# hv3layerMSP.net
KiCad netlist of a schematic drawn in EAGLE
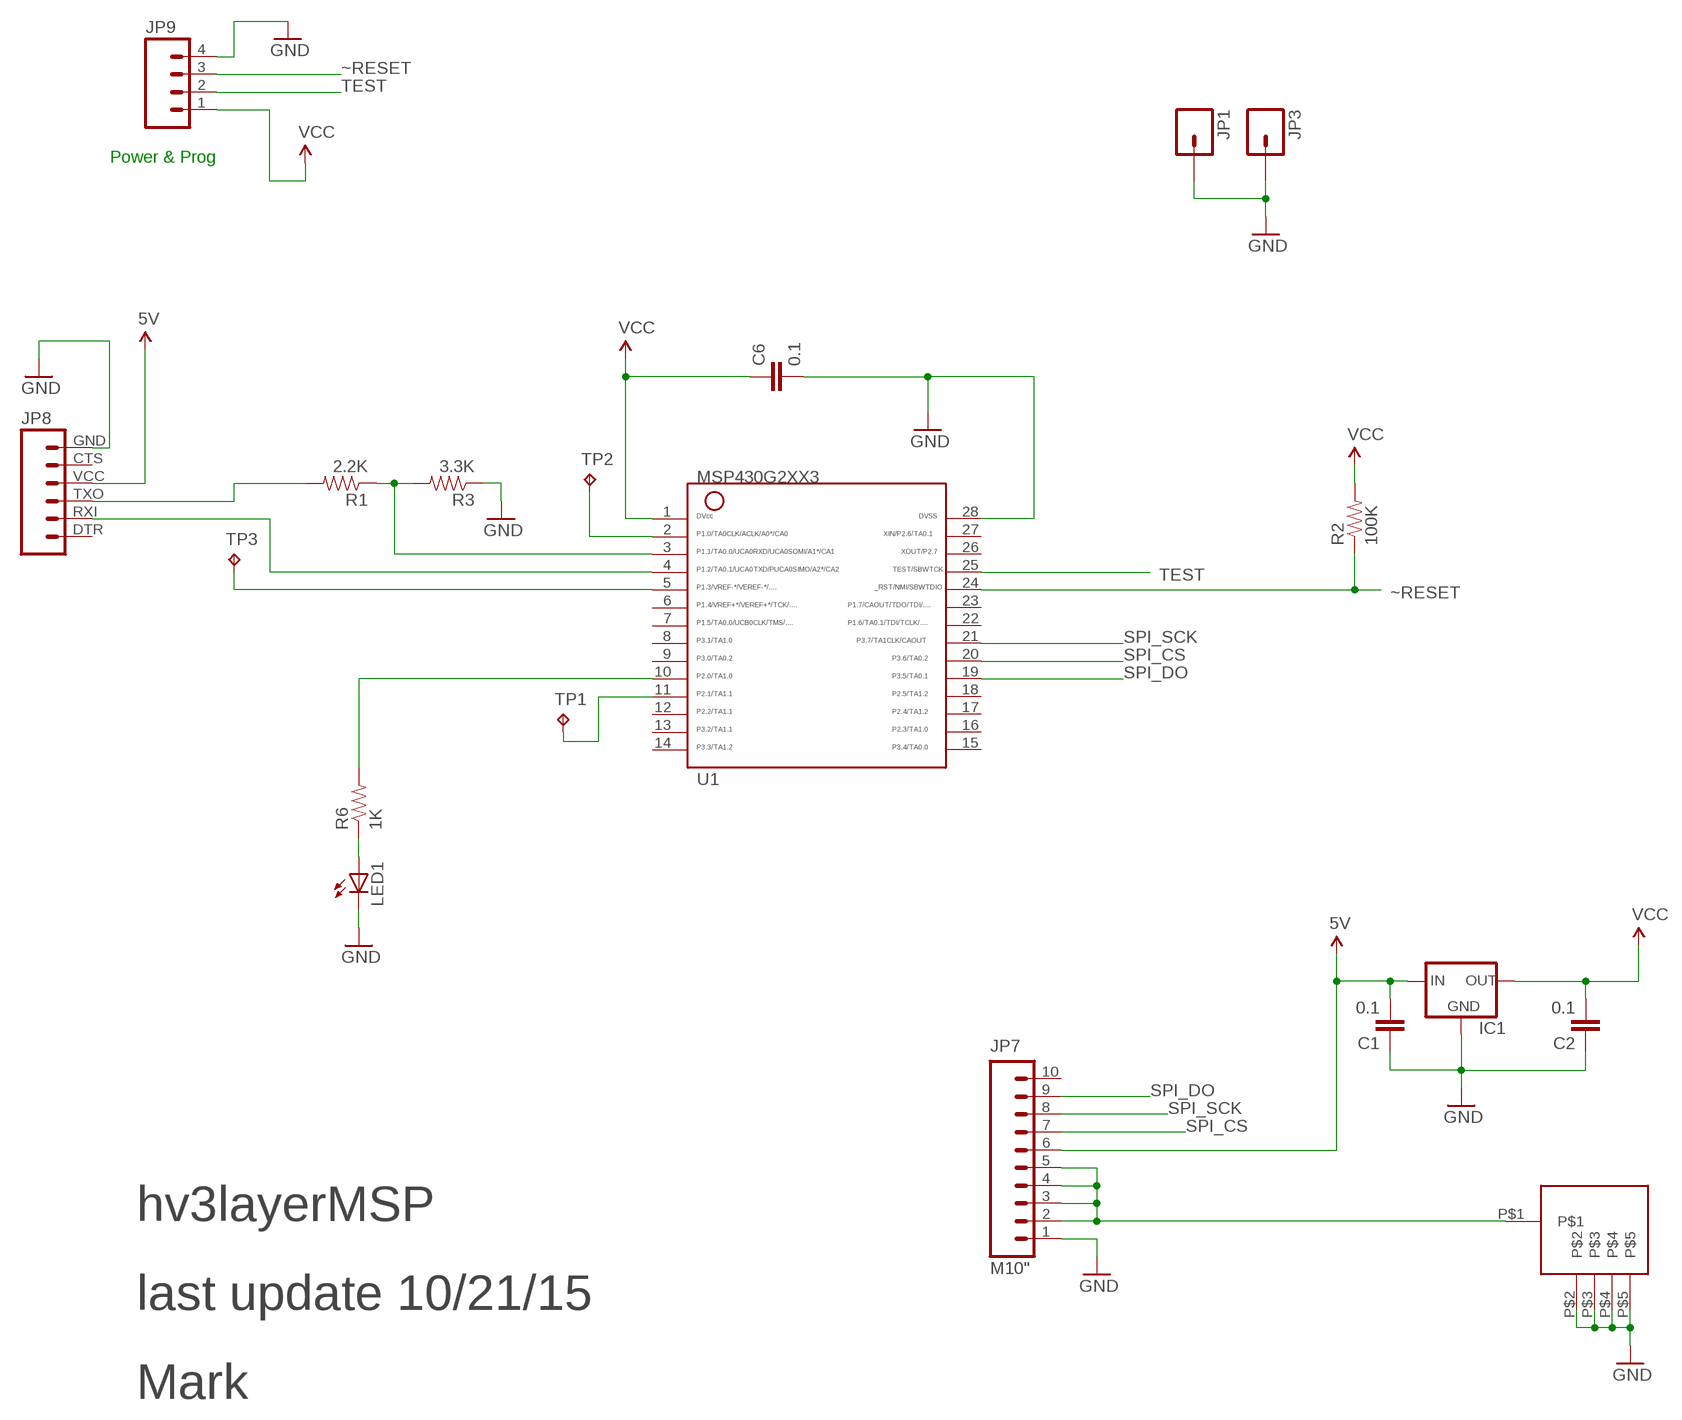
[diagram p0: schematic, sheet 1]

(export (version "E")
  (design (tool "Eeschema 10.0.6"))
  (components
    (comp (ref "C1")
      (value "0.1")
      (footprint "eagle-import:0805")
      (libsource (lib "eagle-import") (part "22UF-6.3V-20%(0805)"))
    )
    (comp (ref "C2")
      (value "0.1")
      (footprint "eagle-import:0805")
      (libsource (lib "eagle-import") (part "22UF-6.3V-20%(0805)"))
    )
    (comp (ref "C6")
      (value "0.1")
      (footprint "eagle-import:0805")
      (libsource (lib "eagle-import") (part "22UF-6.3V-20%(0805)"))
    )
    (comp (ref "IC1")
      (value "XC63FPM")
      (footprint "eagle-import:SOT23")
      (libsource (lib "eagle-import") (part "XC63FPM"))
    )
    (comp (ref "JP1")
      (value "M01PTH")
      (footprint "eagle-import:1X01")
      (libsource (lib "eagle-import") (part "M01PTH"))
    )
    (comp (ref "JP3")
      (value "M01PTH")
      (footprint "eagle-import:1X01")
      (libsource (lib "eagle-import") (part "M01PTH"))
    )
    (comp (ref "JP7")
      (value "M10\"")
      (footprint "eagle-import:1X10")
      (libsource (lib "eagle-import") (part "M10{dblquote}"))
    )
    (comp (ref "JP8")
      (value "M06SIP")
      (footprint "eagle-import:1X06")
      (libsource (lib "eagle-import") (part "M06SIP"))
    )
    (comp (ref "JP9")
      (value "M04PTH")
      (footprint "eagle-import:1X04")
      (libsource (lib "eagle-import") (part "M04PTH"))
    )
    (comp (ref "LED1")
      (value "LEDSML0805")
      (footprint "eagle-import:SML0805")
      (libsource (lib "eagle-import") (part "LEDSML0805"))
    )
    (comp (ref "R1")
      (value "2.2K")
      (footprint "eagle-import:0805")
      (libsource (lib "eagle-import") (part "RESISTOR0805-RES"))
    )
    (comp (ref "R2")
      (value "100K")
      (footprint "eagle-import:0805")
      (libsource (lib "eagle-import") (part "RESISTOR0805-RES"))
    )
    (comp (ref "R3")
      (value "3.3K")
      (footprint "eagle-import:0805")
      (libsource (lib "eagle-import") (part "RESISTOR0805-RES"))
    )
    (comp (ref "R6")
      (value "1K")
      (footprint "eagle-import:0805")
      (libsource (lib "eagle-import") (part "RESISTOR0805-RES"))
    )
    (comp (ref "TP1")
      (value "TPTP10R")
      (footprint "eagle-import:TP10R")
      (libsource (lib "eagle-import") (part "TPTP10R"))
    )
    (comp (ref "TP2")
      (value "TPTP10R")
      (footprint "eagle-import:TP10R")
      (libsource (lib "eagle-import") (part "TPTP10R"))
    )
    (comp (ref "TP3")
      (value "TPTP10R")
      (footprint "eagle-import:TP10R")
      (libsource (lib "eagle-import") (part "TPTP10R"))
    )
    (comp (ref "U$2")
      (value "SMA")
      (footprint "eagle-import:SMA_EDGE")
      (libsource (lib "eagle-import") (part "SMA"))
    )
    (comp (ref "U1")
      (value "G2XX3---PW28")
      (footprint "eagle-import:PW28")
      (libsource (lib "eagle-import") (part "G2XX3---PW28"))
    )
  )
  (nets
    (net (code "1") (name "/SPI_CS") (class "Default")
      (node (ref "JP7") (pin "7") (pinfunction "7_7") (pintype "passive"))
      (node (ref "U1") (pin "20") (pinfunction "20_20") (pintype "bidirectional"))
    )
    (net (code "2") (name "/SPI_DO") (class "Default")
      (node (ref "JP7") (pin "9") (pinfunction "9_9") (pintype "passive"))
      (node (ref "U1") (pin "19") (pinfunction "19_19") (pintype "bidirectional"))
    )
    (net (code "3") (name "/SPI_SCK") (class "Default")
      (node (ref "JP7") (pin "8") (pinfunction "8_8") (pintype "passive"))
      (node (ref "U1") (pin "21") (pinfunction "21_21") (pintype "bidirectional"))
    )
    (net (code "4") (name "/TEST") (class "Default")
      (node (ref "JP9") (pin "2") (pinfunction "2_2") (pintype "passive"))
      (node (ref "U1") (pin "25") (pinfunction "25_25") (pintype "bidirectional"))
    )
    (net (code "5") (name "/~{RESET}") (class "Default")
      (node (ref "JP9") (pin "3") (pinfunction "3_3") (pintype "passive"))
      (node (ref "R2") (pin "1") (pinfunction "1_1") (pintype "passive"))
      (node (ref "U1") (pin "24") (pinfunction "24_24") (pintype "bidirectional"))
    )
    (net (code "6") (name "5V") (class "Default")
      (node (ref "C1") (pin "2") (pinfunction "2_2") (pintype "passive"))
      (node (ref "IC1") (pin "3") (pinfunction "IN_3") (pintype "input"))
      (node (ref "JP7") (pin "6") (pinfunction "6_6") (pintype "passive"))
      (node (ref "JP8") (pin "VCC") (pinfunction "4_VCC") (pintype "passive"))
    )
    (net (code "7") (name "GND") (class "Default")
      (node (ref "C1") (pin "1") (pinfunction "1_1") (pintype "passive"))
      (node (ref "C2") (pin "1") (pinfunction "1_1") (pintype "passive"))
      (node (ref "C6") (pin "2") (pinfunction "2_2") (pintype "passive"))
      (node (ref "IC1") (pin "1") (pinfunction "GND_1") (pintype "input"))
      (node (ref "JP1") (pin "1") (pinfunction "1_1") (pintype "passive"))
      (node (ref "JP3") (pin "1") (pinfunction "1_1") (pintype "passive"))
      (node (ref "JP7") (pin "1") (pinfunction "1_1") (pintype "passive"))
      (node (ref "JP8") (pin "GND") (pinfunction "6_GND") (pintype "passive"))
      (node (ref "JP9") (pin "4") (pinfunction "4_4") (pintype "passive"))
      (node (ref "LED1") (pin "C") (pinfunction "C_C") (pintype "passive"))
      (node (ref "R3") (pin "1") (pinfunction "1_1") (pintype "passive"))
      (node (ref "U$2") (pin "P$2") (pinfunction "P$2_P$2") (pintype "bidirectional"))
      (node (ref "U$2") (pin "P$3") (pinfunction "P$3_P$3") (pintype "bidirectional"))
      (node (ref "U$2") (pin "P$4") (pinfunction "P$4_P$4") (pintype "bidirectional"))
      (node (ref "U$2") (pin "P$5") (pinfunction "P$5_P$5") (pintype "bidirectional"))
      (node (ref "U1") (pin "28") (pinfunction "28_28") (pintype "bidirectional"))
    )
    (net (code "8") (name "Net-(JP7-Pad2)") (class "Default")
      (node (ref "JP7") (pin "2") (pinfunction "2_2") (pintype "passive"))
      (node (ref "JP7") (pin "3") (pinfunction "3_3") (pintype "passive"))
      (node (ref "JP7") (pin "4") (pinfunction "4_4") (pintype "passive"))
      (node (ref "JP7") (pin "5") (pinfunction "5_5") (pintype "passive"))
      (node (ref "U$2") (pin "P$1") (pinfunction "P$1_P$1") (pintype "bidirectional"))
    )
    (net (code "9") (name "Net-(JP8-2)") (class "Default")
      (node (ref "JP8") (pin "RXI") (pinfunction "2_RXI") (pintype "passive"))
      (node (ref "U1") (pin "4") (pinfunction "4_4") (pintype "bidirectional"))
    )
    (net (code "10") (name "Net-(JP8-3)") (class "Default")
      (node (ref "JP8") (pin "TXO") (pinfunction "3_TXO") (pintype "passive"))
      (node (ref "R1") (pin "2") (pinfunction "2_2") (pintype "passive"))
    )
    (net (code "11") (name "Net-(LED1-PadA)") (class "Default")
      (node (ref "LED1") (pin "A") (pinfunction "A_A") (pintype "passive"))
      (node (ref "R6") (pin "1") (pinfunction "1_1") (pintype "passive"))
    )
    (net (code "12") (name "Net-(R1-Pad1)") (class "Default")
      (node (ref "R1") (pin "1") (pinfunction "1_1") (pintype "passive"))
      (node (ref "R3") (pin "2") (pinfunction "2_2") (pintype "passive"))
      (node (ref "U1") (pin "3") (pinfunction "3_3") (pintype "bidirectional"))
    )
    (net (code "13") (name "Net-(R6-Pad2)") (class "Default")
      (node (ref "R6") (pin "2") (pinfunction "2_2") (pintype "passive"))
      (node (ref "U1") (pin "10") (pinfunction "10_10") (pintype "bidirectional"))
    )
    (net (code "14") (name "Net-(TP1-PadTP)") (class "Default")
      (node (ref "TP1") (pin "TP") (pinfunction "TP_TP") (pintype "input"))
      (node (ref "U1") (pin "11") (pinfunction "11_11") (pintype "bidirectional"))
    )
    (net (code "15") (name "Net-(TP2-PadTP)") (class "Default")
      (node (ref "TP2") (pin "TP") (pinfunction "TP_TP") (pintype "input"))
      (node (ref "U1") (pin "2") (pinfunction "2_2") (pintype "bidirectional"))
    )
    (net (code "16") (name "Net-(TP3-PadTP)") (class "Default")
      (node (ref "TP3") (pin "TP") (pinfunction "TP_TP") (pintype "input"))
      (node (ref "U1") (pin "5") (pinfunction "5_5") (pintype "bidirectional"))
    )
    (net (code "17") (name "VCC") (class "Default")
      (node (ref "C2") (pin "2") (pinfunction "2_2") (pintype "passive"))
      (node (ref "C6") (pin "1") (pinfunction "1_1") (pintype "passive"))
      (node (ref "IC1") (pin "2") (pinfunction "OUT_2") (pintype "passive"))
      (node (ref "JP9") (pin "1") (pinfunction "1_1") (pintype "passive"))
      (node (ref "R2") (pin "2") (pinfunction "2_2") (pintype "passive"))
      (node (ref "U1") (pin "1") (pinfunction "1_1") (pintype "bidirectional"))
    )
    (net (code "18") (name "unconnected-(JP7-Pad10)") (class "Default")
      (node (ref "JP7") (pin "10") (pinfunction "10_10") (pintype "passive"))
    )
    (net (code "19") (name "unconnected-(JP8-1-PadDTR)") (class "Default")
      (node (ref "JP8") (pin "DTR") (pinfunction "1_DTR") (pintype "passive"))
    )
    (net (code "20") (name "unconnected-(JP8-5-PadCTS)") (class "Default")
      (node (ref "JP8") (pin "CTS") (pinfunction "5_CTS") (pintype "passive"))
    )
    (net (code "21") (name "unconnected-(U1-Pad6)") (class "Default")
      (node (ref "U1") (pin "6") (pinfunction "6_6") (pintype "bidirectional"))
    )
    (net (code "22") (name "unconnected-(U1-Pad7)") (class "Default")
      (node (ref "U1") (pin "7") (pinfunction "7_7") (pintype "bidirectional"))
    )
    (net (code "23") (name "unconnected-(U1-Pad8)") (class "Default")
      (node (ref "U1") (pin "8") (pinfunction "8_8") (pintype "bidirectional"))
    )
    (net (code "24") (name "unconnected-(U1-Pad9)") (class "Default")
      (node (ref "U1") (pin "9") (pinfunction "9_9") (pintype "bidirectional"))
    )
    (net (code "25") (name "unconnected-(U1-Pad12)") (class "Default")
      (node (ref "U1") (pin "12") (pinfunction "12_12") (pintype "bidirectional"))
    )
    (net (code "26") (name "unconnected-(U1-Pad13)") (class "Default")
      (node (ref "U1") (pin "13") (pinfunction "13_13") (pintype "bidirectional"))
    )
    (net (code "27") (name "unconnected-(U1-Pad14)") (class "Default")
      (node (ref "U1") (pin "14") (pinfunction "14_14") (pintype "bidirectional"))
    )
    (net (code "28") (name "unconnected-(U1-Pad15)") (class "Default")
      (node (ref "U1") (pin "15") (pinfunction "15_15") (pintype "bidirectional"))
    )
    (net (code "29") (name "unconnected-(U1-Pad16)") (class "Default")
      (node (ref "U1") (pin "16") (pinfunction "16_16") (pintype "bidirectional"))
    )
    (net (code "30") (name "unconnected-(U1-Pad17)") (class "Default")
      (node (ref "U1") (pin "17") (pinfunction "17_17") (pintype "bidirectional"))
    )
    (net (code "31") (name "unconnected-(U1-Pad18)") (class "Default")
      (node (ref "U1") (pin "18") (pinfunction "18_18") (pintype "bidirectional"))
    )
    (net (code "32") (name "unconnected-(U1-Pad22)") (class "Default")
      (node (ref "U1") (pin "22") (pinfunction "22_22") (pintype "bidirectional"))
    )
    (net (code "33") (name "unconnected-(U1-Pad23)") (class "Default")
      (node (ref "U1") (pin "23") (pinfunction "23_23") (pintype "bidirectional"))
    )
    (net (code "34") (name "unconnected-(U1-Pad26)") (class "Default")
      (node (ref "U1") (pin "26") (pinfunction "26_26") (pintype "bidirectional"))
    )
    (net (code "35") (name "unconnected-(U1-Pad27)") (class "Default")
      (node (ref "U1") (pin "27") (pinfunction "27_27") (pintype "bidirectional"))
    )
  )
)
